# 6_FPGA_Miscellaneous.net
KiCad netlist of a schematic drawn in Altium Designer
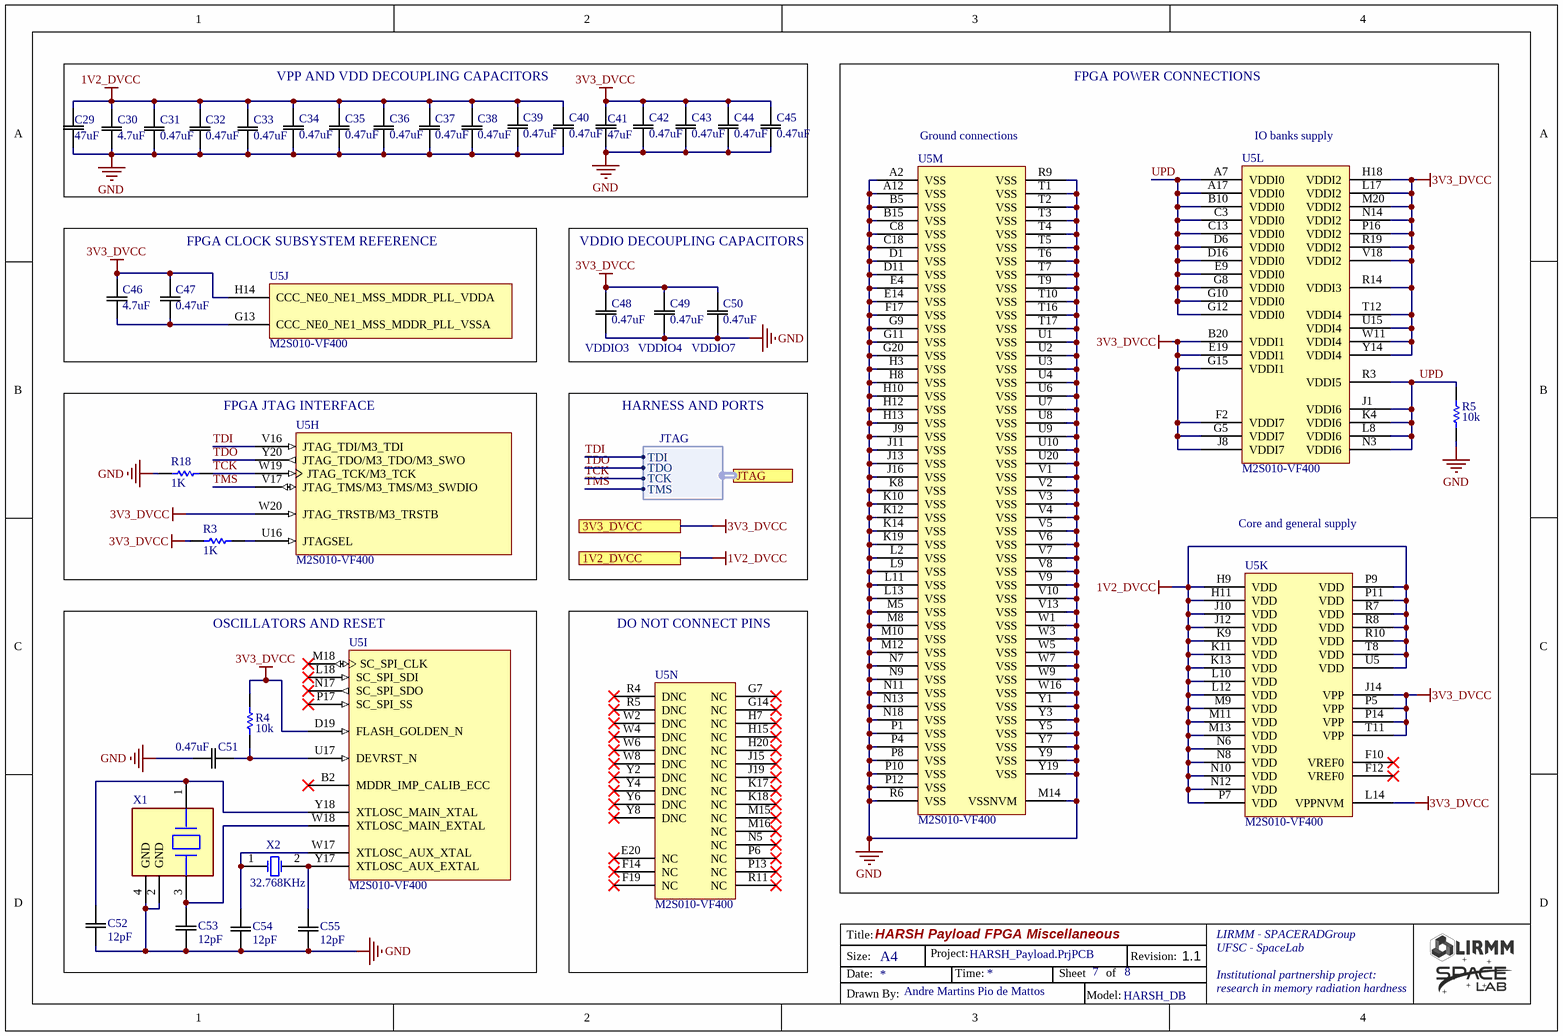
[diagram p0: 6_FPGA_Miscellaneous.SchDoc]

(export (version "E")
  (design (tool "Eeschema 10.0.6"))
  (components
    (comp (ref "C29")
      (value "47uF")
      (footprint "DONE_C0603")
      (description "CAP CER 47UF 6.3V 20% X5R 0603")
      (fields (field (name "PARTNUMBER") "ZRB18AR60J476ME01L") (field (name "VOLTAGE") "10V"))
      (libsource (lib "HARSH_Payload_SchLib") (part "DONE_CAP_47uF_0603_X5R"))
    )
    (comp (ref "C30")
      (value "4.7uF")
      (footprint "DONE_C0603")
      (description "CAP CER 4.7UF 10V 10% X5R 0603")
      (fields (field (name "PARTNUMBER") "C0603C475K8PACTU") (field (name "VOLTAGE") "10V"))
      (libsource (lib "HARSH_Payload_SchLib") (part "DONE_CAP_4.7uF_0603_X5R"))
    )
    (comp (ref "C31")
      (value "0.47uF")
      (footprint "DONE_C0402")
      (description "CAP CER 0.47UF 10V X7R 0402")
      (fields (field (name "MANUFACTURER") "Murata") (field (name "PARTNUMBER") "GRM155R71A474KE01D"))
      (libsource (lib "HARSH_Payload_SchLib") (part "DONE_CAP_0.47uF_0402_X7R"))
    )
    (comp (ref "C32")
      (value "0.47uF")
      (footprint "DONE_C0402")
      (description "CAP CER 0.47UF 10V X7R 0402")
      (fields (field (name "MANUFACTURER") "Murata") (field (name "PARTNUMBER") "GRM155R71A474KE01D"))
      (libsource (lib "HARSH_Payload_SchLib") (part "DONE_CAP_0.47uF_0402_X7R"))
    )
    (comp (ref "C33")
      (value "0.47uF")
      (footprint "DONE_C0402")
      (description "CAP CER 0.47UF 10V X7R 0402")
      (fields (field (name "MANUFACTURER") "Murata") (field (name "PARTNUMBER") "GRM155R71A474KE01D"))
      (libsource (lib "HARSH_Payload_SchLib") (part "DONE_CAP_0.47uF_0402_X7R"))
    )
    (comp (ref "C34")
      (value "0.47uF")
      (footprint "DONE_C0402")
      (description "CAP CER 0.47UF 10V X7R 0402")
      (fields (field (name "MANUFACTURER") "Murata") (field (name "PARTNUMBER") "GRM155R71A474KE01D"))
      (libsource (lib "HARSH_Payload_SchLib") (part "DONE_CAP_0.47uF_0402_X7R"))
    )
    (comp (ref "C35")
      (value "0.47uF")
      (footprint "DONE_C0402")
      (description "CAP CER 0.47UF 10V X7R 0402")
      (fields (field (name "MANUFACTURER") "Murata") (field (name "PARTNUMBER") "GRM155R71A474KE01D"))
      (libsource (lib "HARSH_Payload_SchLib") (part "DONE_CAP_0.47uF_0402_X7R"))
    )
    (comp (ref "C36")
      (value "0.47uF")
      (footprint "DONE_C0402")
      (description "CAP CER 0.47UF 10V X7R 0402")
      (fields (field (name "MANUFACTURER") "Murata") (field (name "PARTNUMBER") "GRM155R71A474KE01D"))
      (libsource (lib "HARSH_Payload_SchLib") (part "DONE_CAP_0.47uF_0402_X7R"))
    )
    (comp (ref "C37")
      (value "0.47uF")
      (footprint "DONE_C0402")
      (description "CAP CER 0.47UF 10V X7R 0402")
      (fields (field (name "MANUFACTURER") "Murata") (field (name "PARTNUMBER") "GRM155R71A474KE01D"))
      (libsource (lib "HARSH_Payload_SchLib") (part "DONE_CAP_0.47uF_0402_X7R"))
    )
    (comp (ref "C38")
      (value "0.47uF")
      (footprint "DONE_C0402")
      (description "CAP CER 0.47UF 10V X7R 0402")
      (fields (field (name "MANUFACTURER") "Murata") (field (name "PARTNUMBER") "GRM155R71A474KE01D"))
      (libsource (lib "HARSH_Payload_SchLib") (part "DONE_CAP_0.47uF_0402_X7R"))
    )
    (comp (ref "C39")
      (value "0.47uF")
      (footprint "DONE_C0402")
      (description "CAP CER 0.47UF 10V X7R 0402")
      (fields (field (name "MANUFACTURER") "Murata") (field (name "PARTNUMBER") "GRM155R71A474KE01D"))
      (libsource (lib "HARSH_Payload_SchLib") (part "DONE_CAP_0.47uF_0402_X7R"))
    )
    (comp (ref "C40")
      (value "0.47uF")
      (footprint "DONE_C0402")
      (description "CAP CER 0.47UF 10V X7R 0402")
      (fields (field (name "MANUFACTURER") "Murata") (field (name "PARTNUMBER") "GRM155R71A474KE01D"))
      (libsource (lib "HARSH_Payload_SchLib") (part "DONE_CAP_0.47uF_0402_X7R"))
    )
    (comp (ref "C41")
      (value "47uF")
      (footprint "DONE_C0603")
      (description "CAP CER 47UF 6.3V 20% X5R 0603")
      (fields (field (name "PARTNUMBER") "ZRB18AR60J476ME01L") (field (name "VOLTAGE") "10V"))
      (libsource (lib "HARSH_Payload_SchLib") (part "DONE_CAP_47uF_0603_X5R"))
    )
    (comp (ref "C42")
      (value "0.47uF")
      (footprint "DONE_C0402")
      (description "CAP CER 0.47UF 10V X7R 0402")
      (fields (field (name "MANUFACTURER") "Murata") (field (name "PARTNUMBER") "GRM155R71A474KE01D"))
      (libsource (lib "HARSH_Payload_SchLib") (part "DONE_CAP_0.47uF_0402_X7R"))
    )
    (comp (ref "C43")
      (value "0.47uF")
      (footprint "DONE_C0402")
      (description "CAP CER 0.47UF 10V X7R 0402")
      (fields (field (name "MANUFACTURER") "Murata") (field (name "PARTNUMBER") "GRM155R71A474KE01D"))
      (libsource (lib "HARSH_Payload_SchLib") (part "DONE_CAP_0.47uF_0402_X7R"))
    )
    (comp (ref "C44")
      (value "0.47uF")
      (footprint "DONE_C0402")
      (description "CAP CER 0.47UF 10V X7R 0402")
      (fields (field (name "MANUFACTURER") "Murata") (field (name "PARTNUMBER") "GRM155R71A474KE01D"))
      (libsource (lib "HARSH_Payload_SchLib") (part "DONE_CAP_0.47uF_0402_X7R"))
    )
    (comp (ref "C45")
      (value "0.47uF")
      (footprint "DONE_C0402")
      (description "CAP CER 0.47UF 10V X7R 0402")
      (fields (field (name "MANUFACTURER") "Murata") (field (name "PARTNUMBER") "GRM155R71A474KE01D"))
      (libsource (lib "HARSH_Payload_SchLib") (part "DONE_CAP_0.47uF_0402_X7R"))
    )
    (comp (ref "C46")
      (value "4.7uF")
      (footprint "DONE_C0603")
      (description "CAP CER 4.7UF 10V 10% X5R 0603")
      (fields (field (name "PARTNUMBER") "C0603C475K8PACTU") (field (name "VOLTAGE") "10V"))
      (libsource (lib "HARSH_Payload_SchLib") (part "DONE_CAP_4.7uF_0603_X5R"))
    )
    (comp (ref "C47")
      (value "0.47uF")
      (footprint "DONE_C0402")
      (description "CAP CER 0.47UF 10V X7R 0402")
      (fields (field (name "MANUFACTURER") "Murata") (field (name "PARTNUMBER") "GRM155R71A474KE01D"))
      (libsource (lib "HARSH_Payload_SchLib") (part "DONE_CAP_0.47uF_0402_X7R"))
    )
    (comp (ref "C48")
      (value "0.47uF")
      (footprint "DONE_C0402")
      (description "CAP CER 0.47UF 10V X7R 0402")
      (fields (field (name "MANUFACTURER") "Murata") (field (name "PARTNUMBER") "GRM155R71A474KE01D"))
      (libsource (lib "HARSH_Payload_SchLib") (part "DONE_CAP_0.47uF_0402_X7R"))
    )
    (comp (ref "C49")
      (value "0.47uF")
      (footprint "DONE_C0402")
      (description "CAP CER 0.47UF 10V X7R 0402")
      (fields (field (name "MANUFACTURER") "Murata") (field (name "PARTNUMBER") "GRM155R71A474KE01D"))
      (libsource (lib "HARSH_Payload_SchLib") (part "DONE_CAP_0.47uF_0402_X7R"))
    )
    (comp (ref "C50")
      (value "0.47uF")
      (footprint "DONE_C0402")
      (description "CAP CER 0.47UF 10V X7R 0402")
      (fields (field (name "MANUFACTURER") "Murata") (field (name "PARTNUMBER") "GRM155R71A474KE01D"))
      (libsource (lib "HARSH_Payload_SchLib") (part "DONE_CAP_0.47uF_0402_X7R"))
    )
    (comp (ref "C51")
      (value "0.47uF")
      (footprint "DONE_C0402")
      (description "CAP CER 0.47UF 10V X7R 0402")
      (fields (field (name "MANUFACTURER") "Murata") (field (name "PARTNUMBER") "GRM155R71A474KE01D"))
      (libsource (lib "HARSH_Payload_SchLib") (part "DONE_CAP_0.47uF_0402_X7R"))
    )
    (comp (ref "C52")
      (value "12pF")
      (footprint "DONE_C0603")
      (description "CAP CER 12PF 50V C0G/NPO 0603")
      (fields (field (name "CAPACITANCE") "12pF") (field (name "PARTNUMBER") "CC0603JRNPO9BN120"))
      (libsource (lib "HARSH_Payload_SchLib") (part "DONE_CAP_12pF_0603"))
    )
    (comp (ref "C53")
      (value "12pF")
      (footprint "DONE_C0603")
      (description "CAP CER 12PF 50V C0G/NPO 0603")
      (fields (field (name "CAPACITANCE") "12pF") (field (name "PARTNUMBER") "CC0603JRNPO9BN120"))
      (libsource (lib "HARSH_Payload_SchLib") (part "DONE_CAP_12pF_0603"))
    )
    (comp (ref "C54")
      (value "12pF")
      (footprint "DONE_C0603")
      (description "CAP CER 12PF 50V C0G/NPO 0603")
      (fields (field (name "CAPACITANCE") "12pF") (field (name "PARTNUMBER") "CC0603JRNPO9BN120"))
      (libsource (lib "HARSH_Payload_SchLib") (part "DONE_CAP_12pF_0603"))
    )
    (comp (ref "C55")
      (value "12pF")
      (footprint "DONE_C0603")
      (description "CAP CER 12PF 50V C0G/NPO 0603")
      (fields (field (name "CAPACITANCE") "12pF") (field (name "PARTNUMBER") "CC0603JRNPO9BN120"))
      (libsource (lib "HARSH_Payload_SchLib") (part "DONE_CAP_12pF_0603"))
    )
    (comp (ref "R3")
      (value "1K")
      (footprint "DONE_R0603")
      (description "RES SMD 1K OHM 1% 1/4W 0603")
      (fields
        (field (name "MANUFACTURER") "Rohm")
        (field (name "MANUFACTURER PART NUMBER") "ESR03EZPF1001")
        (field (name "RESISTANCE") "1K")
      )
      (libsource (lib "HARSH_Payload_SchLib") (part "DONE_RES_1K_0603"))
    )
    (comp (ref "R4")
      (value "10k")
      (footprint "DONE_R0603")
      (description "1/8W 1%  0603 10K")
      (fields
        (field (name "PARTNUMBER") "MCT0603MC1002FP500")
        (field (name "MANUFACTURER") "Vishay Beyschlag")
      )
      (libsource (lib "HARSH_Payload_SchLib") (part "DONE_RES_10K_0603"))
    )
    (comp (ref "R5")
      (value "10k")
      (footprint "DONE_R0603")
      (description "1/8W 1%  0603 10K")
      (fields
        (field (name "PARTNUMBER") "MCT0603MC1002FP500")
        (field (name "MANUFACTURER") "Vishay Beyschlag")
      )
      (libsource (lib "HARSH_Payload_SchLib") (part "DONE_RES_10K_0603"))
    )
    (comp (ref "R18")
      (value "1K")
      (footprint "DONE_R0603")
      (description "RES SMD 1K OHM 1% 1/4W 0603")
      (fields
        (field (name "MANUFACTURER") "Rohm")
        (field (name "MANUFACTURER PART NUMBER") "ESR03EZPF1001")
        (field (name "RESISTANCE") "1K")
      )
      (libsource (lib "HARSH_Payload_SchLib") (part "DONE_RES_1K_0603"))
    )
    (comp (ref "U5")
      (value "M2S010-VF400")
      (footprint "DONE_MCSM_VF_400")
      (fields (field (name "MANUFACTURER") "Microsemi"))
      (libsource (lib "HARSH_Payload_SchLib") (part "DONE_M2S010-VF400"))
    )
    (comp (ref "X1")
      (value "ABM8AIG-12.000MHz-12-D2Z-T")
      (footprint "DONE_XTAL_ABM8AIG")
      (description "Crystals 12MHz 12pF 20ppm ESR 100 -40C +85C")
      (libsource (lib "HARSH_Payload_SchLib") (part "DONE_XTAL_12MHz"))
    )
    (comp (ref "X2")
      (value "32.768KHz")
      (footprint "DONE_XTAL")
      (fields (field (name "PARTNUMBER") "LFXTAL009678REEL") (field (name "PUBLISHER") "Altium Limited"))
      (libsource (lib "HARSH_Payload_SchLib") (part "DONE_XTAL_32.768KHz"))
    )
  )
  (nets
    (net (code "2") (name "/TCK") (class "Default")
      (node (ref "R18") (pin "1") (pinfunction "1_1") (pintype "passive"))
      (node (ref "U5") (pin "W19") (pinfunction "JTAG_TCK/M3_TCK_W19") (pintype "input"))
    )
    (net (code "3") (name "/TDI") (class "Default")
      (node (ref "U5") (pin "V16") (pinfunction "JTAG_TDI/M3_TDI_V16") (pintype "input"))
    )
    (net (code "4") (name "/TDO") (class "Default")
      (node (ref "U5") (pin "Y20") (pinfunction "JTAG_TDO/M3_TDO/M3_SWO_Y20") (pintype "output"))
    )
    (net (code "5") (name "/TMS") (class "Default")
      (node (ref "U5") (pin "V17") (pinfunction "JTAG_TMS/M3_TMS/M3_SWDIO_V17") (pintype "bidirectional"))
    )
    (net (code "6") (name "/UPD") (class "Default")
      (node (ref "R5") (pin "2") (pinfunction "2_2") (pintype "passive"))
      (node (ref "U5") (pin "A17") (pinfunction "VDDI0_A17") (pintype "power_in"))
      (node (ref "U5") (pin "A7") (pinfunction "VDDI0_A7") (pintype "power_in"))
      (node (ref "U5") (pin "B10") (pinfunction "VDDI0_B10") (pintype "power_in"))
      (node (ref "U5") (pin "C13") (pinfunction "VDDI0_C13") (pintype "power_in"))
      (node (ref "U5") (pin "C3") (pinfunction "VDDI0_C3") (pintype "power_in"))
      (node (ref "U5") (pin "D16") (pinfunction "VDDI0_D16") (pintype "power_in"))
      (node (ref "U5") (pin "D6") (pinfunction "VDDI0_D6") (pintype "power_in"))
      (node (ref "U5") (pin "E9") (pinfunction "VDDI0_E9") (pintype "power_in"))
      (node (ref "U5") (pin "G10") (pinfunction "VDDI0_G10") (pintype "power_in"))
      (node (ref "U5") (pin "G12") (pinfunction "VDDI0_G12") (pintype "power_in"))
      (node (ref "U5") (pin "G8") (pinfunction "VDDI0_G8") (pintype "power_in"))
      (node (ref "U5") (pin "J1") (pinfunction "VDDI6_J1") (pintype "power_in"))
      (node (ref "U5") (pin "K4") (pinfunction "VDDI6_K4") (pintype "power_in"))
      (node (ref "U5") (pin "L8") (pinfunction "VDDI6_L8") (pintype "power_in"))
      (node (ref "U5") (pin "N3") (pinfunction "VDDI6_N3") (pintype "power_in"))
      (node (ref "U5") (pin "R3") (pinfunction "VDDI5_R3") (pintype "power_in"))
    )
    (net (code "8") (name "1V2_DVCC") (class "Default")
      (node (ref "C29") (pin "1") (pinfunction "1_1") (pintype "passive"))
      (node (ref "C30") (pin "1") (pinfunction "1_1") (pintype "passive"))
      (node (ref "C31") (pin "1") (pinfunction "1_1") (pintype "passive"))
      (node (ref "C32") (pin "1") (pinfunction "1_1") (pintype "passive"))
      (node (ref "C33") (pin "1") (pinfunction "1_1") (pintype "passive"))
      (node (ref "C34") (pin "1") (pinfunction "1_1") (pintype "passive"))
      (node (ref "C35") (pin "1") (pinfunction "1_1") (pintype "passive"))
      (node (ref "C36") (pin "1") (pinfunction "1_1") (pintype "passive"))
      (node (ref "C37") (pin "1") (pinfunction "1_1") (pintype "passive"))
      (node (ref "C38") (pin "1") (pinfunction "1_1") (pintype "passive"))
      (node (ref "C39") (pin "1") (pinfunction "1_1") (pintype "passive"))
      (node (ref "C40") (pin "1") (pinfunction "1_1") (pintype "passive"))
      (node (ref "U5") (pin "H11") (pinfunction "VDD_H11") (pintype "power_in"))
      (node (ref "U5") (pin "H9") (pinfunction "VDD_H9") (pintype "power_in"))
      (node (ref "U5") (pin "J10") (pinfunction "VDD_J10") (pintype "power_in"))
      (node (ref "U5") (pin "J12") (pinfunction "VDD_J12") (pintype "power_in"))
      (node (ref "U5") (pin "K11") (pinfunction "VDD_K11") (pintype "power_in"))
      (node (ref "U5") (pin "K13") (pinfunction "VDD_K13") (pintype "power_in"))
      (node (ref "U5") (pin "K9") (pinfunction "VDD_K9") (pintype "power_in"))
      (node (ref "U5") (pin "L10") (pinfunction "VDD_L10") (pintype "power_in"))
      (node (ref "U5") (pin "L12") (pinfunction "VDD_L12") (pintype "power_in"))
      (node (ref "U5") (pin "M11") (pinfunction "VDD_M11") (pintype "power_in"))
      (node (ref "U5") (pin "M13") (pinfunction "VDD_M13") (pintype "power_in"))
      (node (ref "U5") (pin "M9") (pinfunction "VDD_M9") (pintype "power_in"))
      (node (ref "U5") (pin "N10") (pinfunction "VDD_N10") (pintype "power_in"))
      (node (ref "U5") (pin "N12") (pinfunction "VDD_N12") (pintype "power_in"))
      (node (ref "U5") (pin "N6") (pinfunction "VDD_N6") (pintype "power_in"))
      (node (ref "U5") (pin "N8") (pinfunction "VDD_N8") (pintype "power_in"))
      (node (ref "U5") (pin "P11") (pinfunction "VDD_P11") (pintype "power_in"))
      (node (ref "U5") (pin "P7") (pinfunction "VDD_P7") (pintype "power_in"))
      (node (ref "U5") (pin "P9") (pinfunction "VDD_P9") (pintype "power_in"))
      (node (ref "U5") (pin "R10") (pinfunction "VDD_R10") (pintype "power_in"))
      (node (ref "U5") (pin "R7") (pinfunction "VDD_R7") (pintype "power_in"))
      (node (ref "U5") (pin "R8") (pinfunction "VDD_R8") (pintype "power_in"))
      (node (ref "U5") (pin "T8") (pinfunction "VDD_T8") (pintype "power_in"))
      (node (ref "U5") (pin "U5") (pinfunction "VDD_U5") (pintype "power_in"))
    )
    (net (code "9") (name "3V3_DVCC") (class "Default")
      (node (ref "C41") (pin "1") (pinfunction "1_1") (pintype "passive"))
      (node (ref "C42") (pin "1") (pinfunction "1_1") (pintype "passive"))
      (node (ref "C43") (pin "1") (pinfunction "1_1") (pintype "passive"))
      (node (ref "C44") (pin "1") (pinfunction "1_1") (pintype "passive"))
      (node (ref "C45") (pin "1") (pinfunction "1_1") (pintype "passive"))
      (node (ref "C46") (pin "1") (pinfunction "1_1") (pintype "passive"))
      (node (ref "C47") (pin "1") (pinfunction "1_1") (pintype "passive"))
      (node (ref "C48") (pin "1") (pinfunction "1_1") (pintype "passive"))
      (node (ref "C49") (pin "1") (pinfunction "1_1") (pintype "passive"))
      (node (ref "C50") (pin "1") (pinfunction "1_1") (pintype "passive"))
      (node (ref "R3") (pin "2") (pinfunction "2_2") (pintype "passive"))
      (node (ref "R4") (pin "2") (pinfunction "2_2") (pintype "passive"))
      (node (ref "U5") (pin "B20") (pinfunction "VDDI1_B20") (pintype "power_in"))
      (node (ref "U5") (pin "D19") (pinfunction "FLASH_GOLDEN_N_D19") (pintype "input"))
      (node (ref "U5") (pin "E19") (pinfunction "VDDI1_E19") (pintype "power_in"))
      (node (ref "U5") (pin "F2") (pinfunction "VDDI7_F2") (pintype "power_in"))
      (node (ref "U5") (pin "G15") (pinfunction "VDDI1_G15") (pintype "power_in"))
      (node (ref "U5") (pin "G5") (pinfunction "VDDI7_G5") (pintype "power_in"))
      (node (ref "U5") (pin "H14") (pinfunction "CCC_NE0_NE1_MSS_MDDR_PLL_VDDA_H14") (pintype "power_in"))
      (node (ref "U5") (pin "H18") (pinfunction "VDDI2_H18") (pintype "power_in"))
      (node (ref "U5") (pin "J14") (pinfunction "VPP_J14") (pintype "power_in"))
      (node (ref "U5") (pin "J8") (pinfunction "VDDI7_J8") (pintype "power_in"))
      (node (ref "U5") (pin "L14") (pinfunction "VPPNVM_L14") (pintype "power_in"))
      (node (ref "U5") (pin "L17") (pinfunction "VDDI2_L17") (pintype "power_in"))
      (node (ref "U5") (pin "M20") (pinfunction "VDDI2_M20") (pintype "power_in"))
      (node (ref "U5") (pin "N14") (pinfunction "VDDI2_N14") (pintype "power_in"))
      (node (ref "U5") (pin "P14") (pinfunction "VPP_P14") (pintype "power_in"))
      (node (ref "U5") (pin "P16") (pinfunction "VDDI2_P16") (pintype "power_in"))
      (node (ref "U5") (pin "P5") (pinfunction "VPP_P5") (pintype "power_in"))
      (node (ref "U5") (pin "R14") (pinfunction "VDDI3_R14") (pintype "power_in"))
      (node (ref "U5") (pin "R19") (pinfunction "VDDI2_R19") (pintype "power_in"))
      (node (ref "U5") (pin "T11") (pinfunction "VPP_T11") (pintype "power_in"))
      (node (ref "U5") (pin "T12") (pinfunction "VDDI4_T12") (pintype "power_in"))
      (node (ref "U5") (pin "U15") (pinfunction "VDDI4_U15") (pintype "power_in"))
      (node (ref "U5") (pin "V18") (pinfunction "VDDI2_V18") (pintype "power_in"))
      (node (ref "U5") (pin "W11") (pinfunction "VDDI4_W11") (pintype "power_in"))
      (node (ref "U5") (pin "W20") (pinfunction "JTAG_TRSTB/M3_TRSTB_W20") (pintype "input"))
      (node (ref "U5") (pin "Y14") (pinfunction "VDDI4_Y14") (pintype "power_in"))
    )
    (net (code "10") (name "GND") (class "Default")
      (node (ref "C29") (pin "2") (pinfunction "2_2") (pintype "passive"))
      (node (ref "C30") (pin "2") (pinfunction "2_2") (pintype "passive"))
      (node (ref "C31") (pin "2") (pinfunction "2_2") (pintype "passive"))
      (node (ref "C32") (pin "2") (pinfunction "2_2") (pintype "passive"))
      (node (ref "C33") (pin "2") (pinfunction "2_2") (pintype "passive"))
      (node (ref "C34") (pin "2") (pinfunction "2_2") (pintype "passive"))
      (node (ref "C35") (pin "2") (pinfunction "2_2") (pintype "passive"))
      (node (ref "C36") (pin "2") (pinfunction "2_2") (pintype "passive"))
      (node (ref "C37") (pin "2") (pinfunction "2_2") (pintype "passive"))
      (node (ref "C38") (pin "2") (pinfunction "2_2") (pintype "passive"))
      (node (ref "C39") (pin "2") (pinfunction "2_2") (pintype "passive"))
      (node (ref "C40") (pin "2") (pinfunction "2_2") (pintype "passive"))
      (node (ref "C41") (pin "2") (pinfunction "2_2") (pintype "passive"))
      (node (ref "C42") (pin "2") (pinfunction "2_2") (pintype "passive"))
      (node (ref "C43") (pin "2") (pinfunction "2_2") (pintype "passive"))
      (node (ref "C44") (pin "2") (pinfunction "2_2") (pintype "passive"))
      (node (ref "C45") (pin "2") (pinfunction "2_2") (pintype "passive"))
      (node (ref "C48") (pin "2") (pinfunction "2_2") (pintype "passive"))
      (node (ref "C49") (pin "2") (pinfunction "2_2") (pintype "passive"))
      (node (ref "C50") (pin "2") (pinfunction "2_2") (pintype "passive"))
      (node (ref "C51") (pin "1") (pinfunction "1_1") (pintype "passive"))
      (node (ref "C52") (pin "2") (pinfunction "2_2") (pintype "passive"))
      (node (ref "C53") (pin "2") (pinfunction "2_2") (pintype "passive"))
      (node (ref "C54") (pin "2") (pinfunction "2_2") (pintype "passive"))
      (node (ref "C55") (pin "2") (pinfunction "2_2") (pintype "passive"))
      (node (ref "R18") (pin "2") (pinfunction "2_2") (pintype "passive"))
      (node (ref "R5") (pin "1") (pinfunction "1_1") (pintype "passive"))
      (node (ref "U5") (pin "A12") (pinfunction "VSS_A12") (pintype "power_in"))
      (node (ref "U5") (pin "A2") (pinfunction "VSS_A2") (pintype "power_in"))
      (node (ref "U5") (pin "B15") (pinfunction "VSS_B15") (pintype "power_in"))
      (node (ref "U5") (pin "B5") (pinfunction "VSS_B5") (pintype "power_in"))
      (node (ref "U5") (pin "C18") (pinfunction "VSS_C18") (pintype "power_in"))
      (node (ref "U5") (pin "C8") (pinfunction "VSS_C8") (pintype "power_in"))
      (node (ref "U5") (pin "D1") (pinfunction "VSS_D1") (pintype "power_in"))
      (node (ref "U5") (pin "D11") (pinfunction "VSS_D11") (pintype "power_in"))
      (node (ref "U5") (pin "E14") (pinfunction "VSS_E14") (pintype "power_in"))
      (node (ref "U5") (pin "E4") (pinfunction "VSS_E4") (pintype "power_in"))
      (node (ref "U5") (pin "F17") (pinfunction "VSS_F17") (pintype "power_in"))
      (node (ref "U5") (pin "G11") (pinfunction "VSS_G11") (pintype "power_in"))
      (node (ref "U5") (pin "G20") (pinfunction "VSS_G20") (pintype "power_in"))
      (node (ref "U5") (pin "G9") (pinfunction "VSS_G9") (pintype "power_in"))
      (node (ref "U5") (pin "H10") (pinfunction "VSS_H10") (pintype "power_in"))
      (node (ref "U5") (pin "H12") (pinfunction "VSS_H12") (pintype "power_in"))
      (node (ref "U5") (pin "H13") (pinfunction "VSS_H13") (pintype "power_in"))
      (node (ref "U5") (pin "H3") (pinfunction "VSS_H3") (pintype "power_in"))
      (node (ref "U5") (pin "H8") (pinfunction "VSS_H8") (pintype "power_in"))
      (node (ref "U5") (pin "J11") (pinfunction "VSS_J11") (pintype "power_in"))
      (node (ref "U5") (pin "J13") (pinfunction "VSS_J13") (pintype "power_in"))
      (node (ref "U5") (pin "J16") (pinfunction "VSS_J16") (pintype "power_in"))
      (node (ref "U5") (pin "J9") (pinfunction "VSS_J9") (pintype "power_in"))
      (node (ref "U5") (pin "K10") (pinfunction "VSS_K10") (pintype "power_in"))
      (node (ref "U5") (pin "K12") (pinfunction "VSS_K12") (pintype "power_in"))
      (node (ref "U5") (pin "K14") (pinfunction "VSS_K14") (pintype "power_in"))
      (node (ref "U5") (pin "K19") (pinfunction "VSS_K19") (pintype "power_in"))
      (node (ref "U5") (pin "K8") (pinfunction "VSS_K8") (pintype "power_in"))
      (node (ref "U5") (pin "L11") (pinfunction "VSS_L11") (pintype "power_in"))
      (node (ref "U5") (pin "L13") (pinfunction "VSS_L13") (pintype "power_in"))
      (node (ref "U5") (pin "L2") (pinfunction "VSS_L2") (pintype "power_in"))
      (node (ref "U5") (pin "L9") (pinfunction "VSS_L9") (pintype "power_in"))
      (node (ref "U5") (pin "M10") (pinfunction "VSS_M10") (pintype "power_in"))
      (node (ref "U5") (pin "M12") (pinfunction "VSS_M12") (pintype "power_in"))
      (node (ref "U5") (pin "M14") (pinfunction "VSSNVM_M14") (pintype "power_in"))
      (node (ref "U5") (pin "M5") (pinfunction "VSS_M5") (pintype "power_in"))
      (node (ref "U5") (pin "M8") (pinfunction "VSS_M8") (pintype "power_in"))
      (node (ref "U5") (pin "N11") (pinfunction "VSS_N11") (pintype "power_in"))
      (node (ref "U5") (pin "N13") (pinfunction "VSS_N13") (pintype "power_in"))
      (node (ref "U5") (pin "N18") (pinfunction "VSS_N18") (pintype "power_in"))
      (node (ref "U5") (pin "N7") (pinfunction "VSS_N7") (pintype "power_in"))
      (node (ref "U5") (pin "N9") (pinfunction "VSS_N9") (pintype "power_in"))
      (node (ref "U5") (pin "P1") (pinfunction "VSS_P1") (pintype "power_in"))
      (node (ref "U5") (pin "P10") (pinfunction "VSS_P10") (pintype "power_in"))
      (node (ref "U5") (pin "P12") (pinfunction "VSS_P12") (pintype "power_in"))
      (node (ref "U5") (pin "P4") (pinfunction "VSS_P4") (pintype "power_in"))
      (node (ref "U5") (pin "P8") (pinfunction "VSS_P8") (pintype "power_in"))
      (node (ref "U5") (pin "R6") (pinfunction "VSS_R6") (pintype "power_in"))
      (node (ref "U5") (pin "R9") (pinfunction "VSS_R9") (pintype "power_in"))
      (node (ref "U5") (pin "T1") (pinfunction "VSS_T1") (pintype "power_in"))
      (node (ref "U5") (pin "T10") (pinfunction "VSS_T10") (pintype "power_in"))
      (node (ref "U5") (pin "T16") (pinfunction "VSS_T16") (pintype "power_in"))
      (node (ref "U5") (pin "T17") (pinfunction "VSS_T17") (pintype "power_in"))
      (node (ref "U5") (pin "T2") (pinfunction "VSS_T2") (pintype "power_in"))
      (node (ref "U5") (pin "T3") (pinfunction "VSS_T3") (pintype "power_in"))
      (node (ref "U5") (pin "T4") (pinfunction "VSS_T4") (pintype "power_in"))
      (node (ref "U5") (pin "T5") (pinfunction "VSS_T5") (pintype "power_in"))
      (node (ref "U5") (pin "T6") (pinfunction "VSS_T6") (pintype "power_in"))
      (node (ref "U5") (pin "T7") (pinfunction "VSS_T7") (pintype "power_in"))
      (node (ref "U5") (pin "T9") (pinfunction "VSS_T9") (pintype "power_in"))
      (node (ref "U5") (pin "U1") (pinfunction "VSS_U1") (pintype "power_in"))
      (node (ref "U5") (pin "U10") (pinfunction "VSS_U10") (pintype "power_in"))
      (node (ref "U5") (pin "U2") (pinfunction "VSS_U2") (pintype "power_in"))
      (node (ref "U5") (pin "U20") (pinfunction "VSS_U20") (pintype "power_in"))
      (node (ref "U5") (pin "U3") (pinfunction "VSS_U3") (pintype "power_in"))
      (node (ref "U5") (pin "U4") (pinfunction "VSS_U4") (pintype "power_in"))
      (node (ref "U5") (pin "U6") (pinfunction "VSS_U6") (pintype "power_in"))
      (node (ref "U5") (pin "U7") (pinfunction "VSS_U7") (pintype "power_in"))
      (node (ref "U5") (pin "U8") (pinfunction "VSS_U8") (pintype "power_in"))
      (node (ref "U5") (pin "U9") (pinfunction "VSS_U9") (pintype "power_in"))
      (node (ref "U5") (pin "V1") (pinfunction "VSS_V1") (pintype "power_in"))
      (node (ref "U5") (pin "V10") (pinfunction "VSS_V10") (pintype "power_in"))
      (node (ref "U5") (pin "V13") (pinfunction "VSS_V13") (pintype "power_in"))
      (node (ref "U5") (pin "V2") (pinfunction "VSS_V2") (pintype "power_in"))
      (node (ref "U5") (pin "V3") (pinfunction "VSS_V3") (pintype "power_in"))
      (node (ref "U5") (pin "V4") (pinfunction "VSS_V4") (pintype "power_in"))
      (node (ref "U5") (pin "V5") (pinfunction "VSS_V5") (pintype "power_in"))
      (node (ref "U5") (pin "V6") (pinfunction "VSS_V6") (pintype "power_in"))
      (node (ref "U5") (pin "V7") (pinfunction "VSS_V7") (pintype "power_in"))
      (node (ref "U5") (pin "V8") (pinfunction "VSS_V8") (pintype "power_in"))
      (node (ref "U5") (pin "V9") (pinfunction "VSS_V9") (pintype "power_in"))
      (node (ref "U5") (pin "W1") (pinfunction "VSS_W1") (pintype "power_in"))
      (node (ref "U5") (pin "W16") (pinfunction "VSS_W16") (pintype "power_in"))
      (node (ref "U5") (pin "W3") (pinfunction "VSS_W3") (pintype "power_in"))
      (node (ref "U5") (pin "W5") (pinfunction "VSS_W5") (pintype "power_in"))
      (node (ref "U5") (pin "W7") (pinfunction "VSS_W7") (pintype "power_in"))
      (node (ref "U5") (pin "W9") (pinfunction "VSS_W9") (pintype "power_in"))
      (node (ref "U5") (pin "Y1") (pinfunction "VSS_Y1") (pintype "power_in"))
      (node (ref "U5") (pin "Y19") (pinfunction "VSS_Y19") (pintype "power_in"))
      (node (ref "U5") (pin "Y3") (pinfunction "VSS_Y3") (pintype "power_in"))
      (node (ref "U5") (pin "Y5") (pinfunction "VSS_Y5") (pintype "power_in"))
      (node (ref "U5") (pin "Y7") (pinfunction "VSS_Y7") (pintype "power_in"))
      (node (ref "U5") (pin "Y9") (pinfunction "VSS_Y9") (pintype "power_in"))
      (node (ref "X1") (pin "2") (pinfunction "GND_2") (pintype "power_in"))
      (node (ref "X1") (pin "4") (pinfunction "GND_4") (pintype "power_in"))
    )
    (net (code "11") (name "Net-(U5H-JTAGSEL)") (class "Default")
      (node (ref "R3") (pin "1") (pinfunction "1_1") (pintype "passive"))
      (node (ref "U5") (pin "U16") (pinfunction "JTAGSEL_U16") (pintype "input"))
    )
    (net (code "12") (name "Net-(U5I-DEVRST_N)") (class "Default")
      (node (ref "C51") (pin "2") (pinfunction "2_2") (pintype "passive"))
      (node (ref "R4") (pin "1") (pinfunction "1_1") (pintype "passive"))
      (node (ref "U5") (pin "U17") (pinfunction "DEVRST_N_U17") (pintype "input"))
    )
    (net (code "13") (name "Net-(U5I-XTLOSC_AUX_EXTAL)") (class "Default")
      (node (ref "C55") (pin "1") (pinfunction "1_1") (pintype "passive"))
      (node (ref "U5") (pin "Y17") (pinfunction "XTLOSC_AUX_EXTAL_Y17") (pintype "passive"))
      (node (ref "X2") (pin "2") (pinfunction "OSC2_2") (pintype "passive"))
    )
    (net (code "14") (name "Net-(U5I-XTLOSC_AUX_XTAL)") (class "Default")
      (node (ref "C54") (pin "1") (pinfunction "1_1") (pintype "passive"))
      (node (ref "U5") (pin "W17") (pinfunction "XTLOSC_AUX_XTAL_W17") (pintype "passive"))
      (node (ref "X2") (pin "1") (pinfunction "OSC1_1") (pintype "passive"))
    )
    (net (code "15") (name "Net-(U5I-XTLOSC_MAIN_EXTAL)") (class "Default")
      (node (ref "C53") (pin "1") (pinfunction "1_1") (pintype "passive"))
      (node (ref "U5") (pin "W18") (pinfunction "XTLOSC_MAIN_EXTAL_W18") (pintype "passive"))
      (node (ref "X1") (pin "3") (pinfunction "2_Crystal_3") (pintype "passive"))
    )
    (net (code "16") (name "Net-(U5I-XTLOSC_MAIN_XTAL)") (class "Default")
      (node (ref "C52") (pin "1") (pinfunction "1_1") (pintype "passive"))
      (node (ref "U5") (pin "Y18") (pinfunction "XTLOSC_MAIN_XTAL_Y18") (pintype "passive"))
      (node (ref "X1") (pin "1") (pinfunction "1_Crystal_1") (pintype "passive"))
    )
    (net (code "17") (name "Net-(U5J-CCC_NE0_NE1_MSS_MDDR_PLL_VSSA)") (class "Default")
      (node (ref "C46") (pin "2") (pinfunction "2_2") (pintype "passive"))
      (node (ref "C47") (pin "2") (pinfunction "2_2") (pintype "passive"))
      (node (ref "U5") (pin "G13") (pinfunction "CCC_NE0_NE1_MSS_MDDR_PLL_VSSA_G13") (pintype "power_in"))
    )
    (net (code "18") (name "unconnected-(U5I-MDDR_IMP_CALIB_ECC-PadB2)") (class "Default")
      (node (ref "U5") (pin "B2") (pinfunction "MDDR_IMP_CALIB_ECC_B2") (pintype "passive+no_connect"))
    )
    (net (code "19") (name "unconnected-(U5I-SC_SPI_CLK-PadM18)") (class "Default")
      (node (ref "U5") (pin "M18") (pinfunction "SC_SPI_CLK_M18") (pintype "bidirectional+no_connect"))
    )
    (net (code "20") (name "unconnected-(U5I-SC_SPI_SDI-PadL18)") (class "Default")
      (node (ref "U5") (pin "L18") (pinfunction "SC_SPI_SDI_L18") (pintype "input+no_connect"))
    )
    (net (code "21") (name "unconnected-(U5I-SC_SPI_SDO-PadN17)") (class "Default")
      (node (ref "U5") (pin "N17") (pinfunction "SC_SPI_SDO_N17") (pintype "output+no_connect"))
    )
    (net (code "22") (name "unconnected-(U5I-SC_SPI_SS-PadP17)") (class "Default")
      (node (ref "U5") (pin "P17") (pinfunction "SC_SPI_SS_P17") (pintype "input+no_connect"))
    )
    (net (code "23") (name "unconnected-(U5K-VREF0-PadF10)") (class "Default")
      (node (ref "U5") (pin "F10") (pinfunction "VREF0_F10") (pintype "power_in+no_connect"))
    )
    (net (code "24") (name "unconnected-(U5K-VREF0-PadF12)") (class "Default")
      (node (ref "U5") (pin "F12") (pinfunction "VREF0_F12") (pintype "power_in+no_connect"))
    )
    (net (code "25") (name "unconnected-(U5N-DNC-PadR4)") (class "Default")
      (node (ref "U5") (pin "R4") (pinfunction "DNC_R4") (pintype "passive+no_connect"))
    )
    (net (code "26") (name "unconnected-(U5N-DNC-PadR5)") (class "Default")
      (node (ref "U5") (pin "R5") (pinfunction "DNC_R5") (pintype "passive+no_connect"))
    )
    (net (code "27") (name "unconnected-(U5N-DNC-PadW2)") (class "Default")
      (node (ref "U5") (pin "W2") (pinfunction "DNC_W2") (pintype "passive+no_connect"))
    )
    (net (code "28") (name "unconnected-(U5N-DNC-PadW4)") (class "Default")
      (node (ref "U5") (pin "W4") (pinfunction "DNC_W4") (pintype "passive+no_connect"))
    )
    (net (code "29") (name "unconnected-(U5N-DNC-PadW6)") (class "Default")
      (node (ref "U5") (pin "W6") (pinfunction "DNC_W6") (pintype "passive+no_connect"))
    )
    (net (code "30") (name "unconnected-(U5N-DNC-PadW8)") (class "Default")
      (node (ref "U5") (pin "W8") (pinfunction "DNC_W8") (pintype "passive+no_connect"))
    )
    (net (code "31") (name "unconnected-(U5N-DNC-PadY2)") (class "Default")
      (node (ref "U5") (pin "Y2") (pinfunction "DNC_Y2") (pintype "passive+no_connect"))
    )
    (net (code "32") (name "unconnected-(U5N-DNC-PadY4)") (class "Default")
      (node (ref "U5") (pin "Y4") (pinfunction "DNC_Y4") (pintype "passive+no_connect"))
    )
    (net (code "33") (name "unconnected-(U5N-DNC-PadY6)") (class "Default")
      (node (ref "U5") (pin "Y6") (pinfunction "DNC_Y6") (pintype "passive+no_connect"))
    )
    (net (code "34") (name "unconnected-(U5N-DNC-PadY8)") (class "Default")
      (node (ref "U5") (pin "Y8") (pinfunction "DNC_Y8") (pintype "passive+no_connect"))
    )
    (net (code "35") (name "unconnected-(U5N-NC-PadE20)") (class "Default")
      (node (ref "U5") (pin "E20") (pinfunction "NC_E20") (pintype "passive+no_connect"))
    )
    (net (code "36") (name "unconnected-(U5N-NC-PadF14)") (class "Default")
      (node (ref "U5") (pin "F14") (pinfunction "NC_F14") (pintype "passive+no_connect"))
    )
    (net (code "37") (name "unconnected-(U5N-NC-PadF19)") (class "Default")
      (node (ref "U5") (pin "F19") (pinfunction "NC_F19") (pintype "passive+no_connect"))
    )
    (net (code "38") (name "unconnected-(U5N-NC-PadG7)") (class "Default")
      (node (ref "U5") (pin "G7") (pinfunction "NC_G7") (pintype "passive+no_connect"))
    )
    (net (code "39") (name "unconnected-(U5N-NC-PadG14)") (class "Default")
      (node (ref "U5") (pin "G14") (pinfunction "NC_G14") (pintype "passive+no_connect"))
    )
    (net (code "40") (name "unconnected-(U5N-NC-PadH7)") (class "Default")
      (node (ref "U5") (pin "H7") (pinfunction "NC_H7") (pintype "passive+no_connect"))
    )
    (net (code "41") (name "unconnected-(U5N-NC-PadH15)") (class "Default")
      (node (ref "U5") (pin "H15") (pinfunction "NC_H15") (pintype "passive+no_connect"))
    )
    (net (code "42") (name "unconnected-(U5N-NC-PadH20)") (class "Default")
      (node (ref "U5") (pin "H20") (pinfunction "NC_H20") (pintype "passive+no_connect"))
    )
    (net (code "43") (name "unconnected-(U5N-NC-PadJ15)") (class "Default")
      (node (ref "U5") (pin "J15") (pinfunction "NC_J15") (pintype "passive+no_connect"))
    )
    (net (code "44") (name "unconnected-(U5N-NC-PadJ19)") (class "Default")
      (node (ref "U5") (pin "J19") (pinfunction "NC_J19") (pintype "passive+no_connect"))
    )
    (net (code "45") (name "unconnected-(U5N-NC-PadK17)") (class "Default")
      (node (ref "U5") (pin "K17") (pinfunction "NC_K17") (pintype "passive+no_connect"))
    )
    (net (code "46") (name "unconnected-(U5N-NC-PadK18)") (class "Default")
      (node (ref "U5") (pin "K18") (pinfunction "NC_K18") (pintype "passive+no_connect"))
    )
    (net (code "47") (name "unconnected-(U5N-NC-PadM15)") (class "Default")
      (node (ref "U5") (pin "M15") (pinfunction "NC_M15") (pintype "passive+no_connect"))
    )
    (net (code "48") (name "unconnected-(U5N-NC-PadM16)") (class "Default")
      (node (ref "U5") (pin "M16") (pinfunction "NC_M16") (pintype "passive+no_connect"))
    )
    (net (code "49") (name "unconnected-(U5N-NC-PadN5)") (class "Default")
      (node (ref "U5") (pin "N5") (pinfunction "NC_N5") (pintype "passive+no_connect"))
    )
    (net (code "50") (name "unconnected-(U5N-NC-PadP6)") (class "Default")
      (node (ref "U5") (pin "P6") (pinfunction "NC_P6") (pintype "passive+no_connect"))
    )
    (net (code "51") (name "unconnected-(U5N-NC-PadP13)") (class "Default")
      (node (ref "U5") (pin "P13") (pinfunction "NC_P13") (pintype "passive+no_connect"))
    )
    (net (code "52") (name "unconnected-(U5N-NC-PadR11)") (class "Default")
      (node (ref "U5") (pin "R11") (pinfunction "NC_R11") (pintype "passive+no_connect"))
    )
  )
)
